# fm_notch.net
KiCad netlist of a schematic drawn in EAGLE
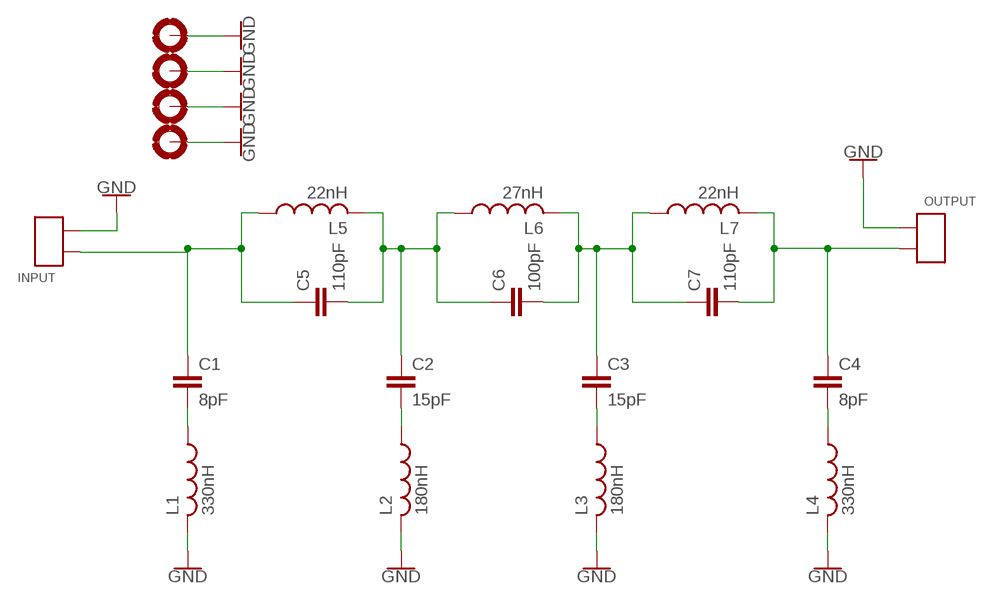
[diagram p0: schematic, sheet 1]

(export (version "E")
  (design (tool "Eeschema 10.0.6"))
  (components
    (comp (ref "C1")
      (value "8pF")
      (footprint "eagle-import:C0805")
      (libsource (lib "eagle-import") (part "C_0805_SMD"))
    )
    (comp (ref "C2")
      (value "15pF")
      (footprint "eagle-import:C0805")
      (libsource (lib "eagle-import") (part "C_0805_SMD"))
    )
    (comp (ref "C3")
      (value "15pF")
      (footprint "eagle-import:C0805")
      (libsource (lib "eagle-import") (part "C_0805_SMD"))
    )
    (comp (ref "C4")
      (value "8pF")
      (footprint "eagle-import:C0805")
      (libsource (lib "eagle-import") (part "C_0805_SMD"))
    )
    (comp (ref "C5")
      (value "110pF")
      (footprint "eagle-import:C0805")
      (libsource (lib "eagle-import") (part "C_0805_SMD"))
    )
    (comp (ref "C6")
      (value "100pF")
      (footprint "eagle-import:C0805")
      (libsource (lib "eagle-import") (part "C_0805_SMD"))
    )
    (comp (ref "C7")
      (value "110pF")
      (footprint "eagle-import:C0805")
      (libsource (lib "eagle-import") (part "C_0805_SMD"))
    )
    (comp (ref "H1")
      (value "MOUNT-PAD-ROUND3.0")
      (footprint "eagle-import:3,0-PAD")
      (libsource (lib "eagle-import") (part "MOUNT-PAD-ROUND3.0"))
    )
    (comp (ref "H2")
      (value "MOUNT-PAD-ROUND3.0")
      (footprint "eagle-import:3,0-PAD")
      (libsource (lib "eagle-import") (part "MOUNT-PAD-ROUND3.0"))
    )
    (comp (ref "H3")
      (value "MOUNT-PAD-ROUND3.0")
      (footprint "eagle-import:3,0-PAD")
      (libsource (lib "eagle-import") (part "MOUNT-PAD-ROUND3.0"))
    )
    (comp (ref "H4")
      (value "MOUNT-PAD-ROUND3.0")
      (footprint "eagle-import:3,0-PAD")
      (libsource (lib "eagle-import") (part "MOUNT-PAD-ROUND3.0"))
    )
    (comp (ref "INPUT")
      (value "INPUT")
      (footprint "eagle-import:2X_SMD_PTH")
      (libsource (lib "eagle-import") (part "2X_SMD_PTH_PIN"))
    )
    (comp (ref "L1")
      (value "330nH")
      (footprint "eagle-import:C0805")
      (libsource (lib "eagle-import") (part "L0805"))
    )
    (comp (ref "L2")
      (value "180nH")
      (footprint "eagle-import:C0805")
      (libsource (lib "eagle-import") (part "L0805"))
    )
    (comp (ref "L3")
      (value "180nH")
      (footprint "eagle-import:C0805")
      (libsource (lib "eagle-import") (part "L0805"))
    )
    (comp (ref "L4")
      (value "330nH")
      (footprint "eagle-import:C0805")
      (libsource (lib "eagle-import") (part "L0805"))
    )
    (comp (ref "L5")
      (value "22nH")
      (footprint "eagle-import:C0805")
      (libsource (lib "eagle-import") (part "L0805"))
    )
    (comp (ref "L6")
      (value "27nH")
      (footprint "eagle-import:C0805")
      (libsource (lib "eagle-import") (part "L0805"))
    )
    (comp (ref "L7")
      (value "22nH")
      (footprint "eagle-import:C0805")
      (libsource (lib "eagle-import") (part "L0805"))
    )
    (comp (ref "OUTPUT")
      (value "2X_SMD_PTH_PIN")
      (footprint "eagle-import:2X_SMD_PTH")
      (libsource (lib "eagle-import") (part "2X_SMD_PTH_PIN"))
    )
  )
  (nets
    (net (code "1") (name "GND") (class "Default")
      (node (ref "H1") (pin "B3,0") (pinfunction "MOUNT_B3,0") (pintype "passive"))
      (node (ref "H2") (pin "B3,0") (pinfunction "MOUNT_B3,0") (pintype "passive"))
      (node (ref "H3") (pin "B3,0") (pinfunction "MOUNT_B3,0") (pintype "passive"))
      (node (ref "H4") (pin "B3,0") (pinfunction "MOUNT_B3,0") (pintype "passive"))
      (node (ref "INPUT") (pin "P$2") (pinfunction "PIN1_P$2") (pintype "bidirectional"))
      (node (ref "INPUT") (pin "T$2") (pinfunction "PIN1_T$2") (pintype "bidirectional"))
      (node (ref "L1") (pin "2") (pinfunction "2_2") (pintype "passive"))
      (node (ref "L2") (pin "2") (pinfunction "2_2") (pintype "passive"))
      (node (ref "L3") (pin "2") (pinfunction "2_2") (pintype "passive"))
      (node (ref "L4") (pin "2") (pinfunction "2_2") (pintype "passive"))
      (node (ref "OUTPUT") (pin "P$1") (pinfunction "PIN0_P$1") (pintype "bidirectional"))
      (node (ref "OUTPUT") (pin "T$1") (pinfunction "PIN0_T$1") (pintype "bidirectional"))
    )
    (net (code "2") (name "Net-(C1-Pad1)") (class "Default")
      (node (ref "C1") (pin "1") (pinfunction "1_1") (pintype "passive"))
      (node (ref "C5") (pin "1") (pinfunction "1_1") (pintype "passive"))
      (node (ref "INPUT") (pin "P$1") (pinfunction "PIN0_P$1") (pintype "bidirectional"))
      (node (ref "INPUT") (pin "T$1") (pinfunction "PIN0_T$1") (pintype "bidirectional"))
      (node (ref "L5") (pin "1") (pinfunction "1_1") (pintype "passive"))
    )
    (net (code "3") (name "Net-(C1-Pad2)") (class "Default")
      (node (ref "C1") (pin "2") (pinfunction "2_2") (pintype "passive"))
      (node (ref "L1") (pin "1") (pinfunction "1_1") (pintype "passive"))
    )
    (net (code "4") (name "Net-(C2-Pad1)") (class "Default")
      (node (ref "C2") (pin "1") (pinfunction "1_1") (pintype "passive"))
      (node (ref "C5") (pin "2") (pinfunction "2_2") (pintype "passive"))
      (node (ref "C6") (pin "1") (pinfunction "1_1") (pintype "passive"))
      (node (ref "L5") (pin "2") (pinfunction "2_2") (pintype "passive"))
      (node (ref "L6") (pin "1") (pinfunction "1_1") (pintype "passive"))
    )
    (net (code "5") (name "Net-(C2-Pad2)") (class "Default")
      (node (ref "C2") (pin "2") (pinfunction "2_2") (pintype "passive"))
      (node (ref "L2") (pin "1") (pinfunction "1_1") (pintype "passive"))
    )
    (net (code "6") (name "Net-(C3-Pad1)") (class "Default")
      (node (ref "C3") (pin "1") (pinfunction "1_1") (pintype "passive"))
      (node (ref "C6") (pin "2") (pinfunction "2_2") (pintype "passive"))
      (node (ref "C7") (pin "1") (pinfunction "1_1") (pintype "passive"))
      (node (ref "L6") (pin "2") (pinfunction "2_2") (pintype "passive"))
      (node (ref "L7") (pin "1") (pinfunction "1_1") (pintype "passive"))
    )
    (net (code "7") (name "Net-(C3-Pad2)") (class "Default")
      (node (ref "C3") (pin "2") (pinfunction "2_2") (pintype "passive"))
      (node (ref "L3") (pin "1") (pinfunction "1_1") (pintype "passive"))
    )
    (net (code "8") (name "Net-(C4-Pad1)") (class "Default")
      (node (ref "C4") (pin "1") (pinfunction "1_1") (pintype "passive"))
      (node (ref "C7") (pin "2") (pinfunction "2_2") (pintype "passive"))
      (node (ref "L7") (pin "2") (pinfunction "2_2") (pintype "passive"))
      (node (ref "OUTPUT") (pin "P$2") (pinfunction "PIN1_P$2") (pintype "bidirectional"))
      (node (ref "OUTPUT") (pin "T$2") (pinfunction "PIN1_T$2") (pintype "bidirectional"))
    )
    (net (code "9") (name "Net-(C4-Pad2)") (class "Default")
      (node (ref "C4") (pin "2") (pinfunction "2_2") (pintype "passive"))
      (node (ref "L4") (pin "1") (pinfunction "1_1") (pintype "passive"))
    )
  )
)
